# FPGA_SDRAM.net
KiCad netlist of a schematic drawn in Altium Designer
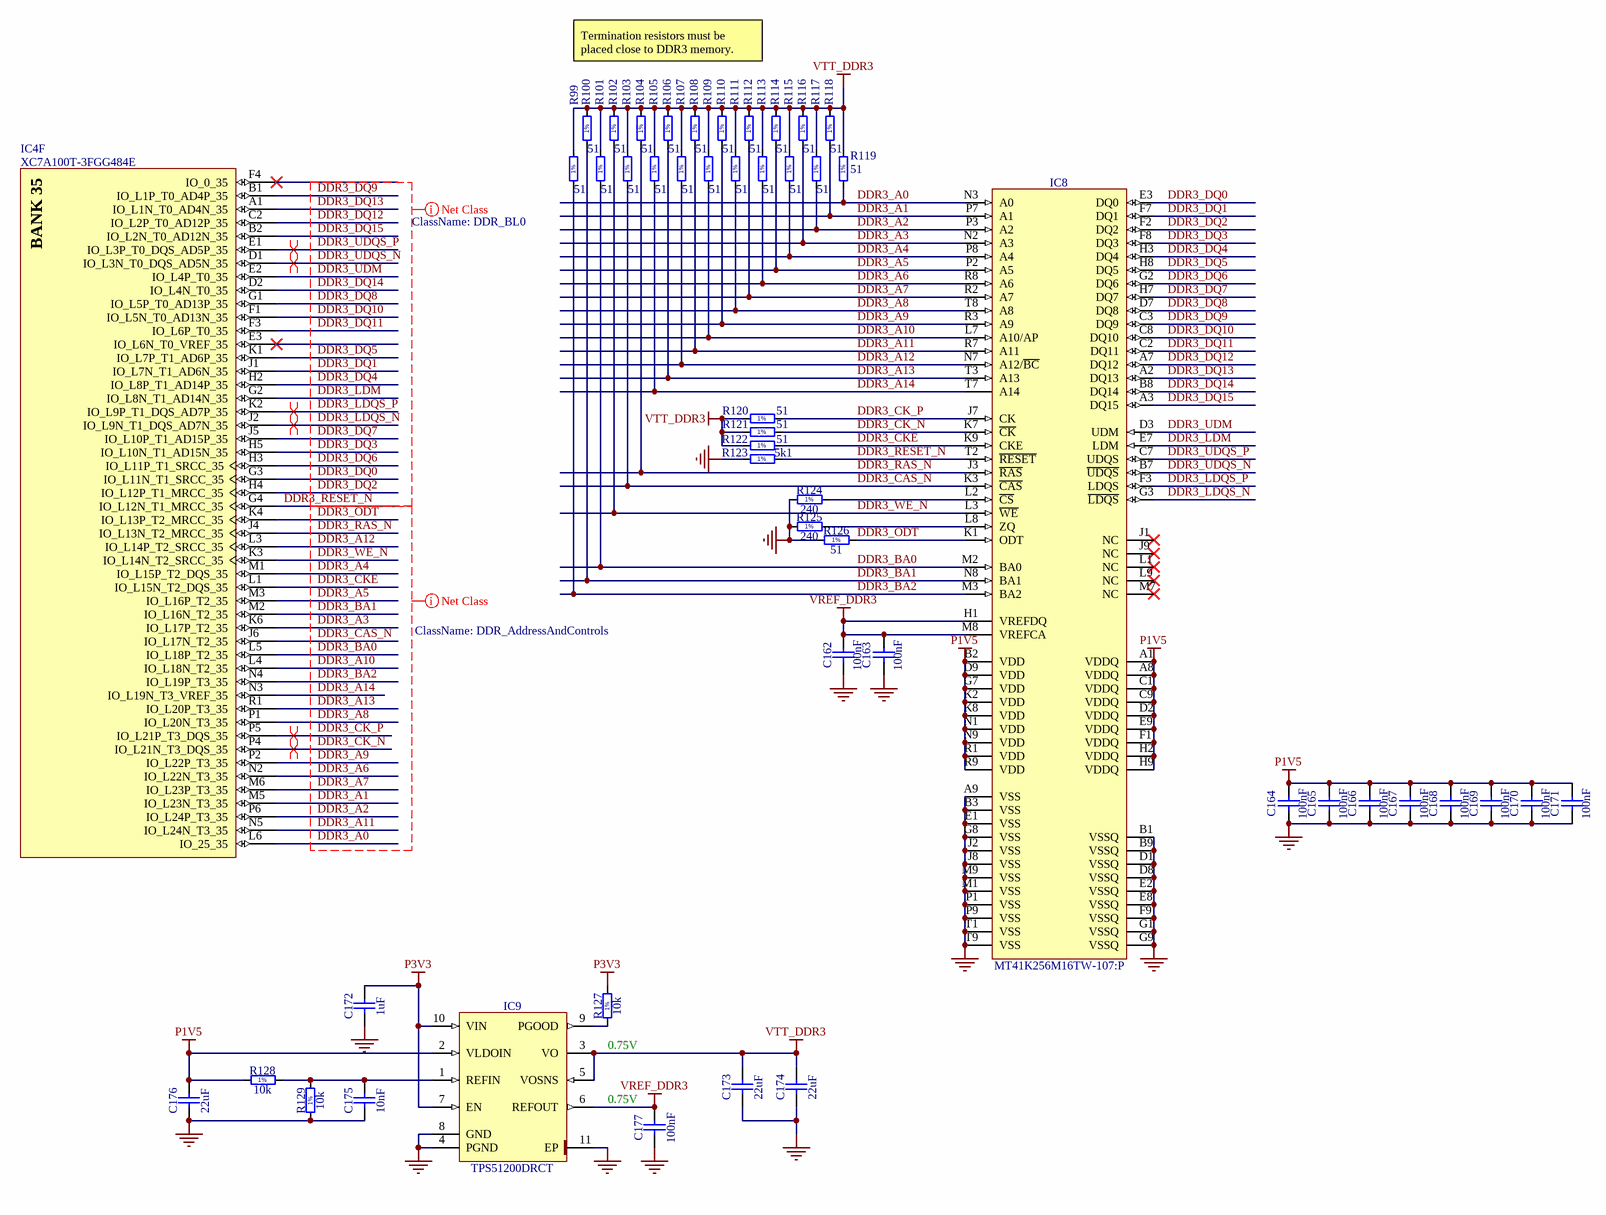
[diagram p0: FPGA_SDRAM.SchDoc]

(export (version "E")
  (design (tool "Eeschema 10.0.6"))
  (components
    (comp (ref "C162")
      (value "100nF")
      (footprint "CAPC0603X33N")
      (description "Non-polarised capacitor")
      (fields
        (field (name "PART NUMBER") "CC0201_100NF_6.3V_10%_X5R")
        (field (name "VOLTAGE") "6.3V")
        (field (name "AUTHOR") "CERN DEM JLC")
      )
      (libsource (lib "Capacitors") (part "Capacitor - non polarized"))
    )
    (comp (ref "C163")
      (value "100nF")
      (footprint "CAPC0603X33N")
      (description "Non-polarised capacitor")
      (fields
        (field (name "PART NUMBER") "CC0201_100NF_6.3V_10%_X5R")
        (field (name "VOLTAGE") "6.3V")
        (field (name "AUTHOR") "CERN DEM JLC")
      )
      (libsource (lib "Capacitors") (part "Capacitor - non polarized"))
    )
    (comp (ref "C164")
      (value "100nF")
      (footprint "CAPC0603X33N")
      (description "Non-polarised capacitor")
      (fields
        (field (name "PART NUMBER") "CC0201_100NF_6.3V_10%_X5R")
        (field (name "VOLTAGE") "6.3V")
        (field (name "AUTHOR") "CERN DEM JLC")
      )
      (libsource (lib "Capacitors") (part "Capacitor - non polarized"))
    )
    (comp (ref "C165")
      (value "100nF")
      (footprint "CAPC0603X33N")
      (description "Non-polarised capacitor")
      (fields
        (field (name "PART NUMBER") "CC0201_100NF_6.3V_10%_X5R")
        (field (name "VOLTAGE") "6.3V")
        (field (name "AUTHOR") "CERN DEM JLC")
      )
      (libsource (lib "Capacitors") (part "Capacitor - non polarized"))
    )
    (comp (ref "C166")
      (value "100nF")
      (footprint "CAPC0603X33N")
      (description "Non-polarised capacitor")
      (fields
        (field (name "PART NUMBER") "CC0201_100NF_6.3V_10%_X5R")
        (field (name "VOLTAGE") "6.3V")
        (field (name "AUTHOR") "CERN DEM JLC")
      )
      (libsource (lib "Capacitors") (part "Capacitor - non polarized"))
    )
    (comp (ref "C167")
      (value "100nF")
      (footprint "CAPC0603X33N")
      (description "Non-polarised capacitor")
      (fields
        (field (name "PART NUMBER") "CC0201_100NF_6.3V_10%_X5R")
        (field (name "VOLTAGE") "6.3V")
        (field (name "AUTHOR") "CERN DEM JLC")
      )
      (libsource (lib "Capacitors") (part "Capacitor - non polarized"))
    )
    (comp (ref "C168")
      (value "100nF")
      (footprint "CAPC0603X33N")
      (description "Non-polarised capacitor")
      (fields
        (field (name "PART NUMBER") "CC0201_100NF_6.3V_10%_X5R")
        (field (name "VOLTAGE") "6.3V")
        (field (name "AUTHOR") "CERN DEM JLC")
      )
      (libsource (lib "Capacitors") (part "Capacitor - non polarized"))
    )
    (comp (ref "C169")
      (value "100nF")
      (footprint "CAPC0603X33N")
      (description "Non-polarised capacitor")
      (fields
        (field (name "PART NUMBER") "CC0201_100NF_6.3V_10%_X5R")
        (field (name "VOLTAGE") "6.3V")
        (field (name "AUTHOR") "CERN DEM JLC")
      )
      (libsource (lib "Capacitors") (part "Capacitor - non polarized"))
    )
    (comp (ref "C170")
      (value "100nF")
      (footprint "CAPC0603X33N")
      (description "Non-polarised capacitor")
      (fields
        (field (name "PART NUMBER") "CC0201_100NF_6.3V_10%_X5R")
        (field (name "VOLTAGE") "6.3V")
        (field (name "AUTHOR") "CERN DEM JLC")
      )
      (libsource (lib "Capacitors") (part "Capacitor - non polarized"))
    )
    (comp (ref "C171")
      (value "100nF")
      (footprint "CAPC0603X33N")
      (description "Non-polarised capacitor")
      (fields
        (field (name "PART NUMBER") "CC0201_100NF_6.3V_10%_X5R")
        (field (name "VOLTAGE") "6.3V")
        (field (name "AUTHOR") "CERN DEM JLC")
      )
      (libsource (lib "Capacitors") (part "Capacitor - non polarized"))
    )
    (comp (ref "C172")
      (value "1uF")
      (footprint "CAPC1005X55N")
      (description "Non-polarised capacitor")
      (fields
        (field (name "PART NUMBER") "CC0402_1UF_16V_10%_X5R")
        (field (name "VOLTAGE") "16V")
        (field (name "AUTHOR") "CERN DEM JLC")
      )
      (libsource (lib "Capacitors") (part "Capacitor - non polarized"))
    )
    (comp (ref "C173")
      (value "22uF")
      (footprint "CAPC1709X100N")
      (description "Non-polarised capacitor")
      (fields
        (field (name "PART NUMBER") "CC0603_22UF_6.3V_20%_X5R")
        (field (name "VOLTAGE") "6.3V")
        (field (name "AUTHOR") "CERN DEM JLC")
      )
      (libsource (lib "Capacitors") (part "Capacitor - non polarized"))
    )
    (comp (ref "C174")
      (value "22uF")
      (footprint "CAPC1709X100N")
      (description "Non-polarised capacitor")
      (fields
        (field (name "PART NUMBER") "CC0603_22UF_6.3V_20%_X5R")
        (field (name "VOLTAGE") "6.3V")
        (field (name "AUTHOR") "CERN DEM JLC")
      )
      (libsource (lib "Capacitors") (part "Capacitor - non polarized"))
    )
    (comp (ref "C175")
      (value "10nF")
      (footprint "CAPC1005X55N")
      (description "Non-polarised capacitor")
      (fields
        (field (name "PART NUMBER") "CC0402_10NF_16V_10%_X7R")
        (field (name "VOLTAGE") "16V")
        (field (name "AUTHOR") "CERN DEM JLC")
      )
      (libsource (lib "Capacitors") (part "Capacitor - non polarized"))
    )
    (comp (ref "C176")
      (value "22uF")
      (footprint "CAPC1709X100N")
      (description "Non-polarised capacitor")
      (fields
        (field (name "PART NUMBER") "CC0603_22UF_6.3V_20%_X5R")
        (field (name "VOLTAGE") "6.3V")
        (field (name "AUTHOR") "CERN DEM JLC")
      )
      (libsource (lib "Capacitors") (part "Capacitor - non polarized"))
    )
    (comp (ref "C177")
      (value "100nF")
      (footprint "CAPC0603X33N")
      (description "Non-polarised capacitor")
      (fields
        (field (name "PART NUMBER") "CC0201_100NF_6.3V_10%_X5R")
        (field (name "VOLTAGE") "6.3V")
        (field (name "AUTHOR") "CERN DEM JLC")
      )
      (libsource (lib "Capacitors") (part "Capacitor - non polarized"))
    )
    (comp (ref "IC4")
      (value "XC7A100T-3FGG484E")
      (footprint "BGA484C100P22X22_2300X2300X260")
      (fields (field (name "MANUFACTURER") "XILINX") (field (name "AUTHOR") "CERN DEM BC"))
      (libsource (lib "ICs And Semiconductors") (part "XC7A100T-3FGG484E"))
    )
    (comp (ref "IC8")
      (value "MT41K256M16TW-107:P")
      (footprint "BGA96C80P9X16_800X1400X120")
      (description "32 Meg x 16 x 8 Banks DDR3L SDRAM")
      (fields (field (name "MANUFACTURER") "MICRON TECHNOLOGY") (field (name "AUTHOR") "CERN DEM MR"))
      (libsource (lib "ICs And Semiconductors") (part "MT41K256M16TW-107{colon}P"))
    )
    (comp (ref "IC9")
      (value "TPS51200DRCT")
      (footprint "TEXAS_DRC (S-PVSON-N10)")
      (description "Sink/Source DDR Termination Regulator")
      (fields (field (name "MANUFACTURER") "TEXAS INSTRUMENTS") (field (name "AUTHOR") "CERN DEM JLC"))
      (libsource (lib "ICs And Semiconductors") (part "TPS51200DRC"))
    )
    (comp (ref "R99")
      (value "51")
      (footprint "RESC1005X40N")
      (description "Resistor - 1%")
      (fields
        (field (name "PART NUMBER") "R0402_51R_1%_0.0625W_100PPM")
        (field (name "POWER") "0.0625W")
        (field (name "AUTHOR") "CERN DEM JLC")
      )
      (libsource (lib "Resistors") (part "Resistor - 1%"))
    )
    (comp (ref "R100")
      (value "51")
      (footprint "RESC1005X40N")
      (description "Resistor - 1%")
      (fields
        (field (name "PART NUMBER") "R0402_51R_1%_0.0625W_100PPM")
        (field (name "POWER") "0.0625W")
        (field (name "AUTHOR") "CERN DEM JLC")
      )
      (libsource (lib "Resistors") (part "Resistor - 1%"))
    )
    (comp (ref "R101")
      (value "51")
      (footprint "RESC1005X40N")
      (description "Resistor - 1%")
      (fields
        (field (name "PART NUMBER") "R0402_51R_1%_0.0625W_100PPM")
        (field (name "POWER") "0.0625W")
        (field (name "AUTHOR") "CERN DEM JLC")
      )
      (libsource (lib "Resistors") (part "Resistor - 1%"))
    )
    (comp (ref "R102")
      (value "51")
      (footprint "RESC1005X40N")
      (description "Resistor - 1%")
      (fields
        (field (name "PART NUMBER") "R0402_51R_1%_0.0625W_100PPM")
        (field (name "POWER") "0.0625W")
        (field (name "AUTHOR") "CERN DEM JLC")
      )
      (libsource (lib "Resistors") (part "Resistor - 1%"))
    )
    (comp (ref "R103")
      (value "51")
      (footprint "RESC1005X40N")
      (description "Resistor - 1%")
      (fields
        (field (name "PART NUMBER") "R0402_51R_1%_0.0625W_100PPM")
        (field (name "POWER") "0.0625W")
        (field (name "AUTHOR") "CERN DEM JLC")
      )
      (libsource (lib "Resistors") (part "Resistor - 1%"))
    )
    (comp (ref "R104")
      (value "51")
      (footprint "RESC1005X40N")
      (description "Resistor - 1%")
      (fields
        (field (name "PART NUMBER") "R0402_51R_1%_0.0625W_100PPM")
        (field (name "POWER") "0.0625W")
        (field (name "AUTHOR") "CERN DEM JLC")
      )
      (libsource (lib "Resistors") (part "Resistor - 1%"))
    )
    (comp (ref "R105")
      (value "51")
      (footprint "RESC1005X40N")
      (description "Resistor - 1%")
      (fields
        (field (name "PART NUMBER") "R0402_51R_1%_0.0625W_100PPM")
        (field (name "POWER") "0.0625W")
        (field (name "AUTHOR") "CERN DEM JLC")
      )
      (libsource (lib "Resistors") (part "Resistor - 1%"))
    )
    (comp (ref "R106")
      (value "51")
      (footprint "RESC1005X40N")
      (description "Resistor - 1%")
      (fields
        (field (name "PART NUMBER") "R0402_51R_1%_0.0625W_100PPM")
        (field (name "POWER") "0.0625W")
        (field (name "AUTHOR") "CERN DEM JLC")
      )
      (libsource (lib "Resistors") (part "Resistor - 1%"))
    )
    (comp (ref "R107")
      (value "51")
      (footprint "RESC1005X40N")
      (description "Resistor - 1%")
      (fields
        (field (name "PART NUMBER") "R0402_51R_1%_0.0625W_100PPM")
        (field (name "POWER") "0.0625W")
        (field (name "AUTHOR") "CERN DEM JLC")
      )
      (libsource (lib "Resistors") (part "Resistor - 1%"))
    )
    (comp (ref "R108")
      (value "51")
      (footprint "RESC1005X40N")
      (description "Resistor - 1%")
      (fields
        (field (name "PART NUMBER") "R0402_51R_1%_0.0625W_100PPM")
        (field (name "POWER") "0.0625W")
        (field (name "AUTHOR") "CERN DEM JLC")
      )
      (libsource (lib "Resistors") (part "Resistor - 1%"))
    )
    (comp (ref "R109")
      (value "51")
      (footprint "RESC1005X40N")
      (description "Resistor - 1%")
      (fields
        (field (name "PART NUMBER") "R0402_51R_1%_0.0625W_100PPM")
        (field (name "POWER") "0.0625W")
        (field (name "AUTHOR") "CERN DEM JLC")
      )
      (libsource (lib "Resistors") (part "Resistor - 1%"))
    )
    (comp (ref "R110")
      (value "51")
      (footprint "RESC1005X40N")
      (description "Resistor - 1%")
      (fields
        (field (name "PART NUMBER") "R0402_51R_1%_0.0625W_100PPM")
        (field (name "POWER") "0.0625W")
        (field (name "AUTHOR") "CERN DEM JLC")
      )
      (libsource (lib "Resistors") (part "Resistor - 1%"))
    )
    (comp (ref "R111")
      (value "51")
      (footprint "RESC1005X40N")
      (description "Resistor - 1%")
      (fields
        (field (name "PART NUMBER") "R0402_51R_1%_0.0625W_100PPM")
        (field (name "POWER") "0.0625W")
        (field (name "AUTHOR") "CERN DEM JLC")
      )
      (libsource (lib "Resistors") (part "Resistor - 1%"))
    )
    (comp (ref "R112")
      (value "51")
      (footprint "RESC1005X40N")
      (description "Resistor - 1%")
      (fields
        (field (name "PART NUMBER") "R0402_51R_1%_0.0625W_100PPM")
        (field (name "POWER") "0.0625W")
        (field (name "AUTHOR") "CERN DEM JLC")
      )
      (libsource (lib "Resistors") (part "Resistor - 1%"))
    )
    (comp (ref "R113")
      (value "51")
      (footprint "RESC1005X40N")
      (description "Resistor - 1%")
      (fields
        (field (name "PART NUMBER") "R0402_51R_1%_0.0625W_100PPM")
        (field (name "POWER") "0.0625W")
        (field (name "AUTHOR") "CERN DEM JLC")
      )
      (libsource (lib "Resistors") (part "Resistor - 1%"))
    )
    (comp (ref "R114")
      (value "51")
      (footprint "RESC1005X40N")
      (description "Resistor - 1%")
      (fields
        (field (name "PART NUMBER") "R0402_51R_1%_0.0625W_100PPM")
        (field (name "POWER") "0.0625W")
        (field (name "AUTHOR") "CERN DEM JLC")
      )
      (libsource (lib "Resistors") (part "Resistor - 1%"))
    )
    (comp (ref "R115")
      (value "51")
      (footprint "RESC1005X40N")
      (description "Resistor - 1%")
      (fields
        (field (name "PART NUMBER") "R0402_51R_1%_0.0625W_100PPM")
        (field (name "POWER") "0.0625W")
        (field (name "AUTHOR") "CERN DEM JLC")
      )
      (libsource (lib "Resistors") (part "Resistor - 1%"))
    )
    (comp (ref "R116")
      (value "51")
      (footprint "RESC1005X40N")
      (description "Resistor - 1%")
      (fields
        (field (name "PART NUMBER") "R0402_51R_1%_0.0625W_100PPM")
        (field (name "POWER") "0.0625W")
        (field (name "AUTHOR") "CERN DEM JLC")
      )
      (libsource (lib "Resistors") (part "Resistor - 1%"))
    )
    (comp (ref "R117")
      (value "51")
      (footprint "RESC1005X40N")
      (description "Resistor - 1%")
      (fields
        (field (name "PART NUMBER") "R0402_51R_1%_0.0625W_100PPM")
        (field (name "POWER") "0.0625W")
        (field (name "AUTHOR") "CERN DEM JLC")
      )
      (libsource (lib "Resistors") (part "Resistor - 1%"))
    )
    (comp (ref "R118")
      (value "51")
      (footprint "RESC1005X40N")
      (description "Resistor - 1%")
      (fields
        (field (name "PART NUMBER") "R0402_51R_1%_0.0625W_100PPM")
        (field (name "POWER") "0.0625W")
        (field (name "AUTHOR") "CERN DEM JLC")
      )
      (libsource (lib "Resistors") (part "Resistor - 1%"))
    )
    (comp (ref "R119")
      (value "51")
      (footprint "RESC1005X40N")
      (description "Resistor - 1%")
      (fields
        (field (name "PART NUMBER") "R0402_51R_1%_0.0625W_100PPM")
        (field (name "POWER") "0.0625W")
        (field (name "AUTHOR") "CERN DEM JLC")
      )
      (libsource (lib "Resistors") (part "Resistor - 1%"))
    )
    (comp (ref "R120")
      (value "51")
      (footprint "RESC1005X40N")
      (description "Resistor - 1%")
      (fields
        (field (name "PART NUMBER") "R0402_51R_1%_0.0625W_100PPM")
        (field (name "POWER") "0.0625W")
        (field (name "AUTHOR") "CERN DEM JLC")
      )
      (libsource (lib "Resistors") (part "Resistor - 1%"))
    )
    (comp (ref "R121")
      (value "51")
      (footprint "RESC1005X40N")
      (description "Resistor - 1%")
      (fields
        (field (name "PART NUMBER") "R0402_51R_1%_0.0625W_100PPM")
        (field (name "POWER") "0.0625W")
        (field (name "AUTHOR") "CERN DEM JLC")
      )
      (libsource (lib "Resistors") (part "Resistor - 1%"))
    )
    (comp (ref "R122")
      (value "51")
      (footprint "RESC1005X40N")
      (description "Resistor - 1%")
      (fields
        (field (name "PART NUMBER") "R0402_51R_1%_0.0625W_100PPM")
        (field (name "POWER") "0.0625W")
        (field (name "AUTHOR") "CERN DEM JLC")
      )
      (libsource (lib "Resistors") (part "Resistor - 1%"))
    )
    (comp (ref "R123")
      (value "5k1")
      (footprint "RESC1005X40N")
      (description "Resistor - 1%")
      (fields
        (field (name "PART NUMBER") "R0402_5K1_1%_0.0625W_100PPM")
        (field (name "POWER") "0.0625W")
        (field (name "AUTHOR") "CERN DEM JLC")
      )
      (libsource (lib "Resistors") (part "Resistor - 1%"))
    )
    (comp (ref "R124")
      (value "240")
      (footprint "RESC1005X40N")
      (description "Resistor - 1%")
      (fields
        (field (name "PART NUMBER") "R0402_240R_1%_0.0625W_100PPM")
        (field (name "POWER") "0.0625W")
        (field (name "AUTHOR") "CERN DEM JLC")
      )
      (libsource (lib "Resistors") (part "Resistor - 1%"))
    )
    (comp (ref "R125")
      (value "240")
      (footprint "RESC1005X40N")
      (description "Resistor - 1%")
      (fields
        (field (name "PART NUMBER") "R0402_240R_1%_0.0625W_100PPM")
        (field (name "POWER") "0.0625W")
        (field (name "AUTHOR") "CERN DEM JLC")
      )
      (libsource (lib "Resistors") (part "Resistor - 1%"))
    )
    (comp (ref "R126")
      (value "51")
      (footprint "RESC1005X40N")
      (description "Resistor - 1%")
      (fields
        (field (name "PART NUMBER") "R0402_51R_1%_0.0625W_100PPM")
        (field (name "POWER") "0.0625W")
        (field (name "AUTHOR") "CERN DEM JLC")
      )
      (libsource (lib "Resistors") (part "Resistor - 1%"))
    )
    (comp (ref "R127")
      (value "10k")
      (footprint "RESC1005X40N")
      (description "Resistor - 1%")
      (fields
        (field (name "PART NUMBER") "R0402_10K_1%_0.0625W_100PPM")
        (field (name "POWER") "0.0625W")
        (field (name "AUTHOR") "CERN DEM JLC")
      )
      (libsource (lib "Resistors") (part "Resistor - 1%"))
    )
    (comp (ref "R128")
      (value "10k")
      (footprint "RESC1005X40N")
      (description "Resistor - 1%")
      (fields
        (field (name "PART NUMBER") "R0402_10K_1%_0.0625W_100PPM")
        (field (name "POWER") "0.0625W")
        (field (name "AUTHOR") "CERN DEM JLC")
      )
      (libsource (lib "Resistors") (part "Resistor - 1%"))
    )
    (comp (ref "R129")
      (value "10k")
      (footprint "RESC1005X40N")
      (description "Resistor - 1%")
      (fields
        (field (name "PART NUMBER") "R0402_10K_1%_0.0625W_100PPM")
        (field (name "POWER") "0.0625W")
        (field (name "AUTHOR") "CERN DEM JLC")
      )
      (libsource (lib "Resistors") (part "Resistor - 1%"))
    )
  )
  (nets
    (net (code "1") (name "/DDR3_A0") (class "Default")
      (node (ref "IC4") (pin "L6") (pinfunction "IO_25_35_L6") (pintype "bidirectional"))
      (node (ref "IC8") (pin "N3") (pinfunction "A0_N3") (pintype "input"))
      (node (ref "R119") (pin "1") (pinfunction "1_1") (pintype "passive"))
    )
    (net (code "2") (name "/DDR3_A1") (class "Default")
      (node (ref "IC4") (pin "M5") (pinfunction "IO_L23N_T3_35_M5") (pintype "bidirectional"))
      (node (ref "IC8") (pin "P7") (pinfunction "A1_P7") (pintype "input"))
      (node (ref "R118") (pin "1") (pinfunction "1_1") (pintype "passive"))
    )
    (net (code "3") (name "/DDR3_A2") (class "Default")
      (node (ref "IC4") (pin "P6") (pinfunction "IO_L24P_T3_35_P6") (pintype "bidirectional"))
      (node (ref "IC8") (pin "P3") (pinfunction "A2_P3") (pintype "input"))
      (node (ref "R117") (pin "1") (pinfunction "1_1") (pintype "passive"))
    )
    (net (code "4") (name "/DDR3_A3") (class "Default")
      (node (ref "IC4") (pin "K6") (pinfunction "IO_L17P_T2_35_K6") (pintype "bidirectional"))
      (node (ref "IC8") (pin "N2") (pinfunction "A3_N2") (pintype "input"))
      (node (ref "R116") (pin "1") (pinfunction "1_1") (pintype "passive"))
    )
    (net (code "5") (name "/DDR3_A4") (class "Default")
      (node (ref "IC4") (pin "M1") (pinfunction "IO_L15P_T2_DQS_35_M1") (pintype "bidirectional"))
      (node (ref "IC8") (pin "P8") (pinfunction "A4_P8") (pintype "input"))
      (node (ref "R115") (pin "1") (pinfunction "1_1") (pintype "passive"))
    )
    (net (code "6") (name "/DDR3_A5") (class "Default")
      (node (ref "IC4") (pin "M3") (pinfunction "IO_L16P_T2_35_M3") (pintype "bidirectional"))
      (node (ref "IC8") (pin "P2") (pinfunction "A5_P2") (pintype "input"))
      (node (ref "R114") (pin "1") (pinfunction "1_1") (pintype "passive"))
    )
    (net (code "7") (name "/DDR3_A6") (class "Default")
      (node (ref "IC4") (pin "N2") (pinfunction "IO_L22N_T3_35_N2") (pintype "bidirectional"))
      (node (ref "IC8") (pin "R8") (pinfunction "A6_R8") (pintype "input"))
      (node (ref "R113") (pin "1") (pinfunction "1_1") (pintype "passive"))
    )
    (net (code "8") (name "/DDR3_A7") (class "Default")
      (node (ref "IC4") (pin "M6") (pinfunction "IO_L23P_T3_35_M6") (pintype "bidirectional"))
      (node (ref "IC8") (pin "R2") (pinfunction "A7_R2") (pintype "input"))
      (node (ref "R112") (pin "1") (pinfunction "1_1") (pintype "passive"))
    )
    (net (code "9") (name "/DDR3_A8") (class "Default")
      (node (ref "IC4") (pin "P1") (pinfunction "IO_L20N_T3_35_P1") (pintype "bidirectional"))
      (node (ref "IC8") (pin "T8") (pinfunction "A8_T8") (pintype "input"))
      (node (ref "R111") (pin "1") (pinfunction "1_1") (pintype "passive"))
    )
    (net (code "10") (name "/DDR3_A9") (class "Default")
      (node (ref "IC4") (pin "P2") (pinfunction "IO_L22P_T3_35_P2") (pintype "bidirectional"))
      (node (ref "IC8") (pin "R3") (pinfunction "A9_R3") (pintype "input"))
      (node (ref "R110") (pin "1") (pinfunction "1_1") (pintype "passive"))
    )
    (net (code "11") (name "/DDR3_A10") (class "Default")
      (node (ref "IC4") (pin "L4") (pinfunction "IO_L18N_T2_35_L4") (pintype "bidirectional"))
      (node (ref "IC8") (pin "L7") (pinfunction "A10/AP_L7") (pintype "input"))
      (node (ref "R109") (pin "1") (pinfunction "1_1") (pintype "passive"))
    )
    (net (code "12") (name "/DDR3_A11") (class "Default")
      (node (ref "IC4") (pin "N5") (pinfunction "IO_L24N_T3_35_N5") (pintype "bidirectional"))
      (node (ref "IC8") (pin "R7") (pinfunction "A11_R7") (pintype "input"))
      (node (ref "R108") (pin "1") (pinfunction "1_1") (pintype "passive"))
    )
    (net (code "13") (name "/DDR3_A12") (class "Default")
      (node (ref "IC4") (pin "L3") (pinfunction "IO_L14P_T2_SRCC_35_L3") (pintype "bidirectional"))
      (node (ref "IC8") (pin "N7") (pinfunction "A12/~{BC}_N7") (pintype "input"))
      (node (ref "R107") (pin "1") (pinfunction "1_1") (pintype "passive"))
    )
    (net (code "14") (name "/DDR3_A13") (class "Default")
      (node (ref "IC4") (pin "R1") (pinfunction "IO_L20P_T3_35_R1") (pintype "bidirectional"))
      (node (ref "IC8") (pin "T3") (pinfunction "A13_T3") (pintype "input"))
      (node (ref "R106") (pin "1") (pinfunction "1_1") (pintype "passive"))
    )
    (net (code "15") (name "/DDR3_A14") (class "Default")
      (node (ref "IC4") (pin "N3") (pinfunction "IO_L19N_T3_VREF_35_N3") (pintype "bidirectional"))
      (node (ref "IC8") (pin "T7") (pinfunction "A14_T7") (pintype "passive"))
      (node (ref "R105") (pin "1") (pinfunction "1_1") (pintype "passive"))
    )
    (net (code "16") (name "/DDR3_BA0") (class "Default")
      (node (ref "IC4") (pin "L5") (pinfunction "IO_L18P_T2_35_L5") (pintype "bidirectional"))
      (node (ref "IC8") (pin "M2") (pinfunction "BA0_M2") (pintype "input"))
      (node (ref "R101") (pin "1") (pinfunction "1_1") (pintype "passive"))
    )
    (net (code "17") (name "/DDR3_BA1") (class "Default")
      (node (ref "IC4") (pin "M2") (pinfunction "IO_L16N_T2_35_M2") (pintype "bidirectional"))
      (node (ref "IC8") (pin "N8") (pinfunction "BA1_N8") (pintype "input"))
      (node (ref "R100") (pin "1") (pinfunction "1_1") (pintype "passive"))
    )
    (net (code "18") (name "/DDR3_BA2") (class "Default")
      (node (ref "IC4") (pin "N4") (pinfunction "IO_L19P_T3_35_N4") (pintype "bidirectional"))
      (node (ref "IC8") (pin "M3") (pinfunction "BA2_M3") (pintype "input"))
      (node (ref "R99") (pin "1") (pinfunction "1_1") (pintype "passive"))
    )
    (net (code "19") (name "/DDR3_CAS_N") (class "Default")
      (node (ref "IC4") (pin "J6") (pinfunction "IO_L17N_T2_35_J6") (pintype "bidirectional"))
      (node (ref "IC8") (pin "K3") (pinfunction "~{CAS}_K3") (pintype "input"))
      (node (ref "R103") (pin "1") (pinfunction "1_1") (pintype "passive"))
    )
    (net (code "20") (name "/DDR3_CKE") (class "Default")
      (node (ref "IC4") (pin "L1") (pinfunction "IO_L15N_T2_DQS_35_L1") (pintype "bidirectional"))
      (node (ref "IC8") (pin "K9") (pinfunction "CKE_K9") (pintype "input"))
      (node (ref "R122") (pin "2") (pinfunction "2_2") (pintype "passive"))
    )
    (net (code "21") (name "/DDR3_CK_N") (class "Default")
      (node (ref "IC4") (pin "P4") (pinfunction "IO_L21N_T3_DQS_35_P4") (pintype "bidirectional"))
      (node (ref "IC8") (pin "K7") (pinfunction "~{CK}_K7") (pintype "input"))
      (node (ref "R121") (pin "2") (pinfunction "2_2") (pintype "passive"))
    )
    (net (code "22") (name "/DDR3_CK_P") (class "Default")
      (node (ref "IC4") (pin "P5") (pinfunction "IO_L21P_T3_DQS_35_P5") (pintype "bidirectional"))
      (node (ref "IC8") (pin "J7") (pinfunction "CK_J7") (pintype "input"))
      (node (ref "R120") (pin "2") (pinfunction "2_2") (pintype "passive"))
    )
    (net (code "23") (name "/DDR3_DQ0") (class "Default")
      (node (ref "IC4") (pin "G3") (pinfunction "IO_L11N_T1_SRCC_35_G3") (pintype "bidirectional"))
      (node (ref "IC8") (pin "E3") (pinfunction "DQ0_E3") (pintype "bidirectional"))
    )
    (net (code "24") (name "/DDR3_DQ1") (class "Default")
      (node (ref "IC4") (pin "J1") (pinfunction "IO_L7N_T1_AD6N_35_J1") (pintype "bidirectional"))
      (node (ref "IC8") (pin "F7") (pinfunction "DQ1_F7") (pintype "bidirectional"))
    )
    (net (code "25") (name "/DDR3_DQ2") (class "Default")
      (node (ref "IC4") (pin "H4") (pinfunction "IO_L12P_T1_MRCC_35_H4") (pintype "bidirectional"))
      (node (ref "IC8") (pin "F2") (pinfunction "DQ2_F2") (pintype "bidirectional"))
    )
    (net (code "26") (name "/DDR3_DQ3") (class "Default")
      (node (ref "IC4") (pin "H5") (pinfunction "IO_L10N_T1_AD15N_35_H5") (pintype "bidirectional"))
      (node (ref "IC8") (pin "F8") (pinfunction "DQ3_F8") (pintype "bidirectional"))
    )
    (net (code "27") (name "/DDR3_DQ4") (class "Default")
      (node (ref "IC4") (pin "H2") (pinfunction "IO_L8P_T1_AD14P_35_H2") (pintype "bidirectional"))
      (node (ref "IC8") (pin "H3") (pinfunction "DQ4_H3") (pintype "bidirectional"))
    )
    (net (code "28") (name "/DDR3_DQ5") (class "Default")
      (node (ref "IC4") (pin "K1") (pinfunction "IO_L7P_T1_AD6P_35_K1") (pintype "bidirectional"))
      (node (ref "IC8") (pin "H8") (pinfunction "DQ5_H8") (pintype "bidirectional"))
    )
    (net (code "29") (name "/DDR3_DQ6") (class "Default")
      (node (ref "IC4") (pin "H3") (pinfunction "IO_L11P_T1_SRCC_35_H3") (pintype "bidirectional"))
      (node (ref "IC8") (pin "G2") (pinfunction "DQ6_G2") (pintype "bidirectional"))
    )
    (net (code "30") (name "/DDR3_DQ7") (class "Default")
      (node (ref "IC4") (pin "J5") (pinfunction "IO_L10P_T1_AD15P_35_J5") (pintype "bidirectional"))
      (node (ref "IC8") (pin "H7") (pinfunction "DQ7_H7") (pintype "bidirectional"))
    )
    (net (code "31") (name "/DDR3_DQ8") (class "Default")
      (node (ref "IC4") (pin "G1") (pinfunction "IO_L5P_T0_AD13P_35_G1") (pintype "bidirectional"))
      (node (ref "IC8") (pin "D7") (pinfunction "DQ8_D7") (pintype "bidirectional"))
    )
    (net (code "32") (name "/DDR3_DQ9") (class "Default")
      (node (ref "IC4") (pin "B1") (pinfunction "IO_L1P_T0_AD4P_35_B1") (pintype "bidirectional"))
      (node (ref "IC8") (pin "C3") (pinfunction "DQ9_C3") (pintype "bidirectional"))
    )
    (net (code "33") (name "/DDR3_DQ10") (class "Default")
      (node (ref "IC4") (pin "F1") (pinfunction "IO_L5N_T0_AD13N_35_F1") (pintype "bidirectional"))
      (node (ref "IC8") (pin "C8") (pinfunction "DQ10_C8") (pintype "bidirectional"))
    )
    (net (code "34") (name "/DDR3_DQ11") (class "Default")
      (node (ref "IC4") (pin "F3") (pinfunction "IO_L6P_T0_35_F3") (pintype "bidirectional"))
      (node (ref "IC8") (pin "C2") (pinfunction "DQ11_C2") (pintype "bidirectional"))
    )
    (net (code "35") (name "/DDR3_DQ12") (class "Default")
      (node (ref "IC4") (pin "C2") (pinfunction "IO_L2P_T0_AD12P_35_C2") (pintype "bidirectional"))
      (node (ref "IC8") (pin "A7") (pinfunction "DQ12_A7") (pintype "bidirectional"))
    )
    (net (code "36") (name "/DDR3_DQ13") (class "Default")
      (node (ref "IC4") (pin "A1") (pinfunction "IO_L1N_T0_AD4N_35_A1") (pintype "bidirectional"))
      (node (ref "IC8") (pin "A2") (pinfunction "DQ13_A2") (pintype "bidirectional"))
    )
    (net (code "37") (name "/DDR3_DQ14") (class "Default")
      (node (ref "IC4") (pin "D2") (pinfunction "IO_L4N_T0_35_D2") (pintype "bidirectional"))
      (node (ref "IC8") (pin "B8") (pinfunction "DQ14_B8") (pintype "bidirectional"))
    )
    (net (code "38") (name "/DDR3_DQ15") (class "Default")
      (node (ref "IC4") (pin "B2") (pinfunction "IO_L2N_T0_AD12N_35_B2") (pintype "bidirectional"))
      (node (ref "IC8") (pin "A3") (pinfunction "DQ15_A3") (pintype "bidirectional"))
    )
    (net (code "39") (name "/DDR3_LDM") (class "Default")
      (node (ref "IC4") (pin "G2") (pinfunction "IO_L8N_T1_AD14N_35_G2") (pintype "bidirectional"))
      (node (ref "IC8") (pin "E7") (pinfunction "LDM_E7") (pintype "input"))
    )
    (net (code "40") (name "/DDR3_LDQS_N") (class "Default")
      (node (ref "IC4") (pin "J2") (pinfunction "IO_L9N_T1_DQS_AD7N_35_J2") (pintype "bidirectional"))
      (node (ref "IC8") (pin "G3") (pinfunction "~{LDQS}_G3") (pintype "bidirectional"))
    )
    (net (code "41") (name "/DDR3_LDQS_P") (class "Default")
      (node (ref "IC4") (pin "K2") (pinfunction "IO_L9P_T1_DQS_AD7P_35_K2") (pintype "bidirectional"))
      (node (ref "IC8") (pin "F3") (pinfunction "LDQS_F3") (pintype "bidirectional"))
    )
    (net (code "42") (name "/DDR3_ODT") (class "Default")
      (node (ref "IC4") (pin "K4") (pinfunction "IO_L13P_T2_MRCC_35_K4") (pintype "bidirectional"))
      (node (ref "IC8") (pin "K1") (pinfunction "ODT_K1") (pintype "input"))
      (node (ref "R126") (pin "2") (pinfunction "2_2") (pintype "passive"))
    )
    (net (code "43") (name "/DDR3_RAS_N") (class "Default")
      (node (ref "IC4") (pin "J4") (pinfunction "IO_L13N_T2_MRCC_35_J4") (pintype "bidirectional"))
      (node (ref "IC8") (pin "J3") (pinfunction "~{RAS}_J3") (pintype "input"))
      (node (ref "R104") (pin "1") (pinfunction "1_1") (pintype "passive"))
    )
    (net (code "44") (name "/DDR3_RESET_N") (class "Default")
      (node (ref "IC4") (pin "G4") (pinfunction "IO_L12N_T1_MRCC_35_G4") (pintype "bidirectional"))
      (node (ref "IC8") (pin "T2") (pinfunction "~{RESET}_T2") (pintype "input"))
      (node (ref "R123") (pin "2") (pinfunction "2_2") (pintype "passive"))
    )
    (net (code "45") (name "/DDR3_UDM") (class "Default")
      (node (ref "IC4") (pin "E2") (pinfunction "IO_L4P_T0_35_E2") (pintype "bidirectional"))
      (node (ref "IC8") (pin "D3") (pinfunction "UDM_D3") (pintype "input"))
    )
    (net (code "46") (name "/DDR3_UDQS_N") (class "Default")
      (node (ref "IC4") (pin "D1") (pinfunction "IO_L3N_T0_DQS_AD5N_35_D1") (pintype "bidirectional"))
      (node (ref "IC8") (pin "B7") (pinfunction "~{UDQS}_B7") (pintype "bidirectional"))
    )
    (net (code "47") (name "/DDR3_UDQS_P") (class "Default")
      (node (ref "IC4") (pin "E1") (pinfunction "IO_L3P_T0_DQS_AD5P_35_E1") (pintype "bidirectional"))
      (node (ref "IC8") (pin "C7") (pinfunction "UDQS_C7") (pintype "bidirectional"))
    )
    (net (code "48") (name "/DDR3_WE_N") (class "Default")
      (node (ref "IC4") (pin "K3") (pinfunction "IO_L14N_T2_SRCC_35_K3") (pintype "bidirectional"))
      (node (ref "IC8") (pin "L3") (pinfunction "~{WE}_L3") (pintype "input"))
      (node (ref "R102") (pin "1") (pinfunction "1_1") (pintype "passive"))
    )
    (net (code "49") (name "GND") (class "Default")
      (node (ref "C162") (pin "1") (pinfunction "1_1") (pintype "passive"))
      (node (ref "C163") (pin "1") (pinfunction "1_1") (pintype "passive"))
      (node (ref "C164") (pin "1") (pinfunction "1_1") (pintype "passive"))
      (node (ref "C165") (pin "1") (pinfunction "1_1") (pintype "passive"))
      (node (ref "C166") (pin "1") (pinfunction "1_1") (pintype "passive"))
      (node (ref "C167") (pin "1") (pinfunction "1_1") (pintype "passive"))
      (node (ref "C168") (pin "1") (pinfunction "1_1") (pintype "passive"))
      (node (ref "C169") (pin "1") (pinfunction "1_1") (pintype "passive"))
      (node (ref "C170") (pin "1") (pinfunction "1_1") (pintype "passive"))
      (node (ref "C171") (pin "1") (pinfunction "1_1") (pintype "passive"))
      (node (ref "C172") (pin "1") (pinfunction "1_1") (pintype "passive"))
      (node (ref "C173") (pin "1") (pinfunction "1_1") (pintype "passive"))
      (node (ref "C174") (pin "1") (pinfunction "1_1") (pintype "passive"))
      (node (ref "C175") (pin "1") (pinfunction "1_1") (pintype "passive"))
      (node (ref "C176") (pin "1") (pinfunction "1_1") (pintype "passive"))
      (node (ref "C177") (pin "1") (pinfunction "1_1") (pintype "passive"))
      (node (ref "IC8") (pin "A9") (pinfunction "VSS_A9") (pintype "power_in"))
      (node (ref "IC8") (pin "B1") (pinfunction "VSSQ_B1") (pintype "power_in"))
      (node (ref "IC8") (pin "B3") (pinfunction "VSS_B3") (pintype "power_in"))
      (node (ref "IC8") (pin "B9") (pinfunction "VSSQ_B9") (pintype "power_in"))
      (node (ref "IC8") (pin "D1") (pinfunction "VSSQ_D1") (pintype "power_in"))
      (node (ref "IC8") (pin "D8") (pinfunction "VSSQ_D8") (pintype "power_in"))
      (node (ref "IC8") (pin "E1") (pinfunction "VSS_E1") (pintype "power_in"))
      (node (ref "IC8") (pin "E2") (pinfunction "VSSQ_E2") (pintype "power_in"))
      (node (ref "IC8") (pin "E8") (pinfunction "VSSQ_E8") (pintype "power_in"))
      (node (ref "IC8") (pin "F9") (pinfunction "VSSQ_F9") (pintype "power_in"))
      (node (ref "IC8") (pin "G1") (pinfunction "VSSQ_G1") (pintype "power_in"))
      (node (ref "IC8") (pin "G8") (pinfunction "VSS_G8") (pintype "power_in"))
      (node (ref "IC8") (pin "G9") (pinfunction "VSSQ_G9") (pintype "power_in"))
      (node (ref "IC8") (pin "J2") (pinfunction "VSS_J2") (pintype "power_in"))
      (node (ref "IC8") (pin "J8") (pinfunction "VSS_J8") (pintype "power_in"))
      (node (ref "IC8") (pin "M1") (pinfunction "VSS_M1") (pintype "power_in"))
      (node (ref "IC8") (pin "M9") (pinfunction "VSS_M9") (pintype "power_in"))
      (node (ref "IC8") (pin "P1") (pinfunction "VSS_P1") (pintype "power_in"))
      (node (ref "IC8") (pin "P9") (pinfunction "VSS_P9") (pintype "power_in"))
      (node (ref "IC8") (pin "T1") (pinfunction "VSS_T1") (pintype "power_in"))
      (node (ref "IC8") (pin "T9") (pinfunction "VSS_T9") (pintype "power_in"))
      (node (ref "IC9") (pin "11") (pinfunction "EP_11") (pintype "power_in"))
      (node (ref "IC9") (pin "4") (pinfunction "PGND_4") (pintype "power_in"))
      (node (ref "IC9") (pin "8") (pinfunction "GND_8") (pintype "power_in"))
      (node (ref "R123") (pin "1") (pinfunction "1_1") (pintype "passive"))
      (node (ref "R124") (pin "1") (pinfunction "1_1") (pintype "passive"))
      (node (ref "R125") (pin "1") (pinfunction "1_1") (pintype "passive"))
      (node (ref "R126") (pin "1") (pinfunction "1_1") (pintype "passive"))
      (node (ref "R129") (pin "1") (pinfunction "1_1") (pintype "passive"))
    )
    (net (code "50") (name "Net-(IC8-ZQ)") (class "Default")
      (node (ref "IC8") (pin "L8") (pinfunction "ZQ_L8") (pintype "input"))
      (node (ref "R125") (pin "2") (pinfunction "2_2") (pintype "passive"))
    )
    (net (code "51") (name "Net-(IC8-~{CS})") (class "Default")
      (node (ref "IC8") (pin "L2") (pinfunction "~{CS}_L2") (pintype "input"))
      (node (ref "R124") (pin "2") (pinfunction "2_2") (pintype "passive"))
    )
    (net (code "52") (name "Net-(IC9-PGOOD)") (class "Default")
      (node (ref "IC9") (pin "9") (pinfunction "PGOOD_9") (pintype "output"))
      (node (ref "R127") (pin "1") (pinfunction "1_1") (pintype "passive"))
    )
    (net (code "53") (name "Net-(IC9-REFIN)") (class "Default")
      (node (ref "C175") (pin "2") (pinfunction "2_2") (pintype "passive"))
      (node (ref "IC9") (pin "1") (pinfunction "REFIN_1") (pintype "input"))
      (node (ref "R128") (pin "2") (pinfunction "2_2") (pintype "passive"))
      (node (ref "R129") (pin "2") (pinfunction "2_2") (pintype "passive"))
    )
    (net (code "54") (name "P1V5") (class "Default")
      (node (ref "C164") (pin "2") (pinfunction "2_2") (pintype "passive"))
      (node (ref "C165") (pin "2") (pinfunction "2_2") (pintype "passive"))
      (node (ref "C166") (pin "2") (pinfunction "2_2") (pintype "passive"))
      (node (ref "C167") (pin "2") (pinfunction "2_2") (pintype "passive"))
      (node (ref "C168") (pin "2") (pinfunction "2_2") (pintype "passive"))
      (node (ref "C169") (pin "2") (pinfunction "2_2") (pintype "passive"))
      (node (ref "C170") (pin "2") (pinfunction "2_2") (pintype "passive"))
      (node (ref "C171") (pin "2") (pinfunction "2_2") (pintype "passive"))
      (node (ref "C176") (pin "2") (pinfunction "2_2") (pintype "passive"))
      (node (ref "IC8") (pin "A1") (pinfunction "VDDQ_A1") (pintype "power_in"))
      (node (ref "IC8") (pin "A8") (pinfunction "VDDQ_A8") (pintype "power_in"))
      (node (ref "IC8") (pin "B2") (pinfunction "VDD_B2") (pintype "power_in"))
      (node (ref "IC8") (pin "C1") (pinfunction "VDDQ_C1") (pintype "power_in"))
      (node (ref "IC8") (pin "C9") (pinfunction "VDDQ_C9") (pintype "power_in"))
      (node (ref "IC8") (pin "D2") (pinfunction "VDDQ_D2") (pintype "power_in"))
      (node (ref "IC8") (pin "D9") (pinfunction "VDD_D9") (pintype "power_in"))
      (node (ref "IC8") (pin "E9") (pinfunction "VDDQ_E9") (pintype "power_in"))
      (node (ref "IC8") (pin "F1") (pinfunction "VDDQ_F1") (pintype "power_in"))
      (node (ref "IC8") (pin "G7") (pinfunction "VDD_G7") (pintype "power_in"))
      (node (ref "IC8") (pin "H2") (pinfunction "VDDQ_H2") (pintype "power_in"))
      (node (ref "IC8") (pin "H9") (pinfunction "VDDQ_H9") (pintype "power_in"))
      (node (ref "IC8") (pin "K2") (pinfunction "VDD_K2") (pintype "power_in"))
      (node (ref "IC8") (pin "K8") (pinfunction "VDD_K8") (pintype "power_in"))
      (node (ref "IC8") (pin "N1") (pinfunction "VDD_N1") (pintype "power_in"))
      (node (ref "IC8") (pin "N9") (pinfunction "VDD_N9") (pintype "power_in"))
      (node (ref "IC8") (pin "R1") (pinfunction "VDD_R1") (pintype "power_in"))
      (node (ref "IC8") (pin "R9") (pinfunction "VDD_R9") (pintype "power_in"))
      (node (ref "IC9") (pin "2") (pinfunction "VLDOIN_2") (pintype "input"))
      (node (ref "R128") (pin "1") (pinfunction "1_1") (pintype "passive"))
    )
    (net (code "55") (name "P3V3") (class "Default")
      (node (ref "C172") (pin "2") (pinfunction "2_2") (pintype "passive"))
      (node (ref "IC9") (pin "10") (pinfunction "VIN_10") (pintype "input"))
      (node (ref "IC9") (pin "7") (pinfunction "EN_7") (pintype "input"))
      (node (ref "R127") (pin "2") (pinfunction "2_2") (pintype "passive"))
    )
    (net (code "56") (name "VREF_DDR3") (class "Default")
      (node (ref "C162") (pin "2") (pinfunction "2_2") (pintype "passive"))
      (node (ref "C163") (pin "2") (pinfunction "2_2") (pintype "passive"))
      (node (ref "C177") (pin "2") (pinfunction "2_2") (pintype "passive"))
      (node (ref "IC8") (pin "H1") (pinfunction "VREFDQ_H1") (pintype "power_in"))
      (node (ref "IC8") (pin "M8") (pinfunction "VREFCA_M8") (pintype "power_in"))
      (node (ref "IC9") (pin "6") (pinfunction "REFOUT_6") (pintype "output"))
    )
    (net (code "57") (name "VTT_DDR3") (class "Default")
      (node (ref "C173") (pin "2") (pinfunction "2_2") (pintype "passive"))
      (node (ref "C174") (pin "2") (pinfunction "2_2") (pintype "passive"))
      (node (ref "IC9") (pin "3") (pinfunction "VO_3") (pintype "power_in"))
      (node (ref "IC9") (pin "5") (pinfunction "VOSNS_5") (pintype "input"))
      (node (ref "R100") (pin "2") (pinfunction "2_2") (pintype "passive"))
      (node (ref "R101") (pin "2") (pinfunction "2_2") (pintype "passive"))
      (node (ref "R102") (pin "2") (pinfunction "2_2") (pintype "passive"))
      (node (ref "R103") (pin "2") (pinfunction "2_2") (pintype "passive"))
      (node (ref "R104") (pin "2") (pinfunction "2_2") (pintype "passive"))
      (node (ref "R105") (pin "2") (pinfunction "2_2") (pintype "passive"))
      (node (ref "R106") (pin "2") (pinfunction "2_2") (pintype "passive"))
      (node (ref "R107") (pin "2") (pinfunction "2_2") (pintype "passive"))
      (node (ref "R108") (pin "2") (pinfunction "2_2") (pintype "passive"))
      (node (ref "R109") (pin "2") (pinfunction "2_2") (pintype "passive"))
      (node (ref "R110") (pin "2") (pinfunction "2_2") (pintype "passive"))
      (node (ref "R111") (pin "2") (pinfunction "2_2") (pintype "passive"))
      (node (ref "R112") (pin "2") (pinfunction "2_2") (pintype "passive"))
      (node (ref "R113") (pin "2") (pinfunction "2_2") (pintype "passive"))
      (node (ref "R114") (pin "2") (pinfunction "2_2") (pintype "passive"))
      (node (ref "R115") (pin "2") (pinfunction "2_2") (pintype "passive"))
      (node (ref "R116") (pin "2") (pinfunction "2_2") (pintype "passive"))
      (node (ref "R117") (pin "2") (pinfunction "2_2") (pintype "passive"))
      (node (ref "R118") (pin "2") (pinfunction "2_2") (pintype "passive"))
      (node (ref "R119") (pin "2") (pinfunction "2_2") (pintype "passive"))
      (node (ref "R120") (pin "1") (pinfunction "1_1") (pintype "passive"))
      (node (ref "R121") (pin "1") (pinfunction "1_1") (pintype "passive"))
      (node (ref "R122") (pin "1") (pinfunction "1_1") (pintype "passive"))
      (node (ref "R99") (pin "2") (pinfunction "2_2") (pintype "passive"))
    )
    (net (code "58") (name "unconnected-(IC4F-IO_0_35-PadF4)") (class "Default")
      (node (ref "IC4") (pin "F4") (pinfunction "IO_0_35_F4") (pintype "bidirectional+no_connect"))
    )
    (net (code "59") (name "unconnected-(IC4F-IO_L6N_T0_VREF_35-PadE3)") (class "Default")
      (node (ref "IC4") (pin "E3") (pinfunction "IO_L6N_T0_VREF_35_E3") (pintype "bidirectional+no_connect"))
    )
    (net (code "60") (name "unconnected-(IC8-NC-PadJ1)") (class "Default")
      (node (ref "IC8") (pin "J1") (pinfunction "NC_J1") (pintype "passive+no_connect"))
    )
    (net (code "61") (name "unconnected-(IC8-NC-PadJ9)") (class "Default")
      (node (ref "IC8") (pin "J9") (pinfunction "NC_J9") (pintype "passive+no_connect"))
    )
    (net (code "62") (name "unconnected-(IC8-NC-PadL1)") (class "Default")
      (node (ref "IC8") (pin "L1") (pinfunction "NC_L1") (pintype "passive+no_connect"))
    )
    (net (code "63") (name "unconnected-(IC8-NC-PadL9)") (class "Default")
      (node (ref "IC8") (pin "L9") (pinfunction "NC_L9") (pintype "passive+no_connect"))
    )
    (net (code "64") (name "unconnected-(IC8-NC-PadM7)") (class "Default")
      (node (ref "IC8") (pin "M7") (pinfunction "NC_M7") (pintype "passive+no_connect"))
    )
  )
)
